# coildriver_new.net
KiCad netlist of a schematic drawn in EasyEDA Pro
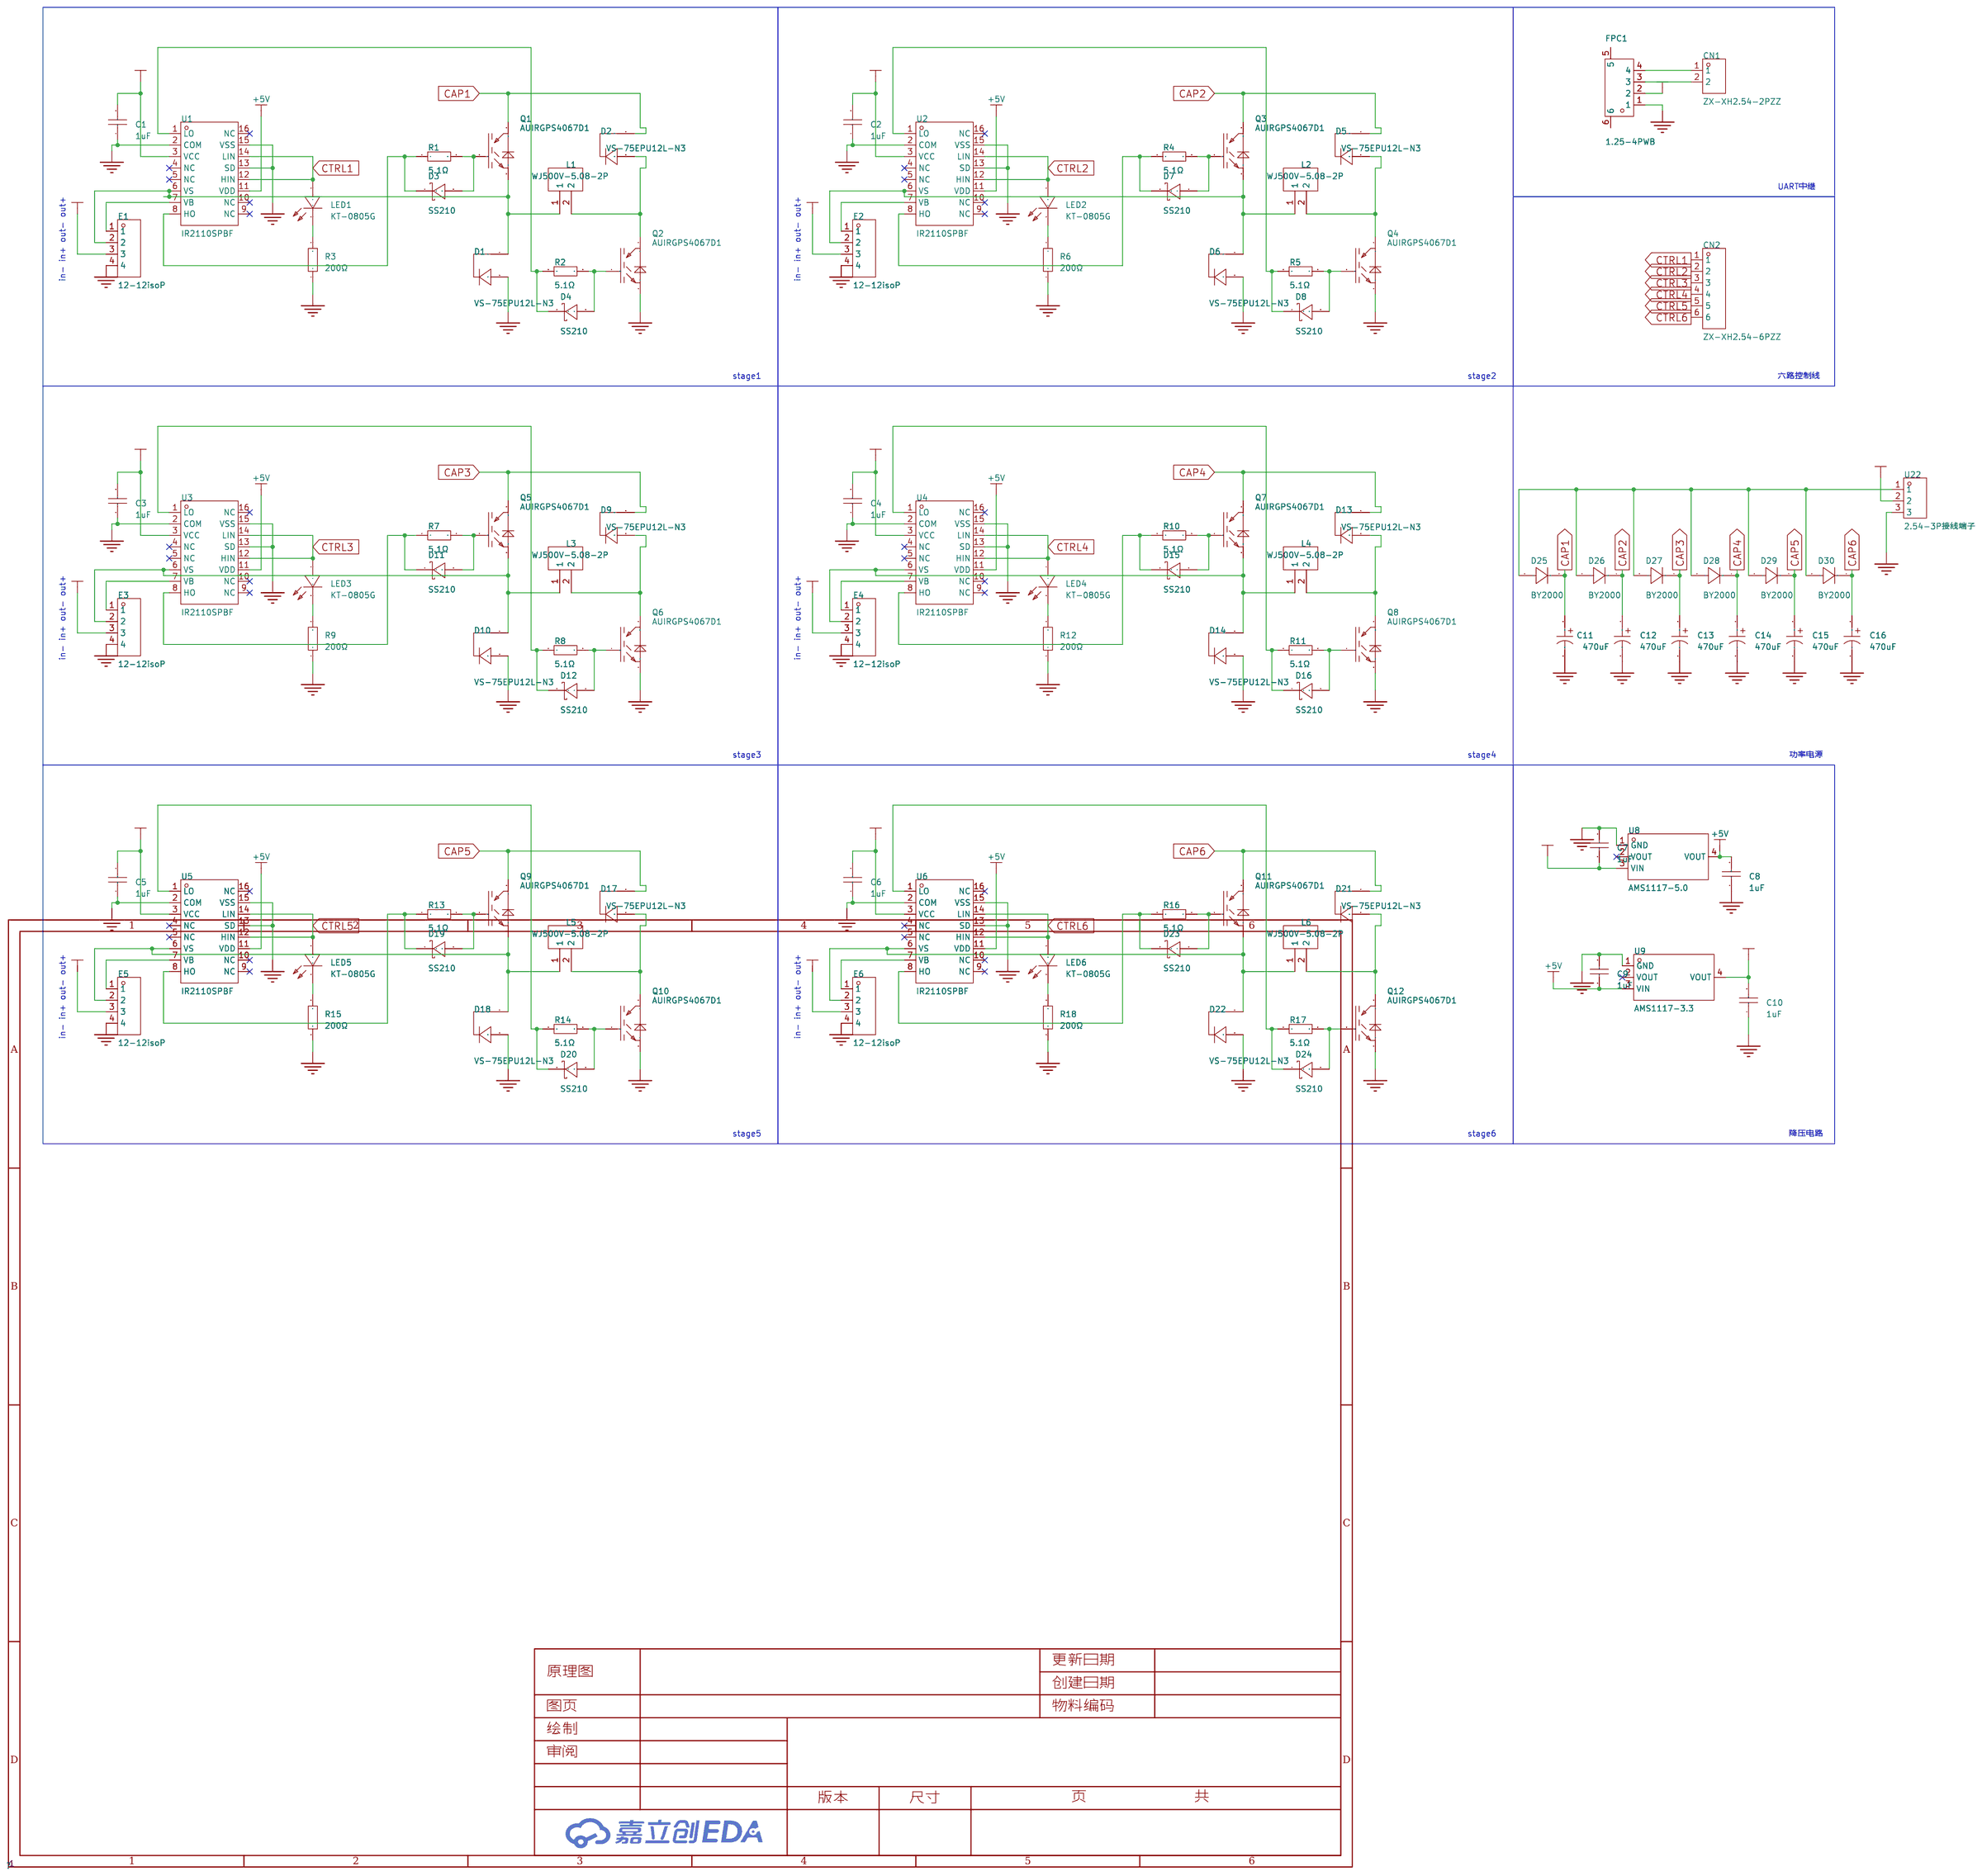
[diagram p0: schematic sheet]

(export (version "E")
  (design (tool "Eeschema 10.0.6"))
  (components
    (comp (ref "C1")
      (value "1uF")
      (footprint "easyedapro:C0805")
      (description "容值:1uF;精度:±10%;额定电压:50V;材质(温度系数):X7R;")
      (fields
        (field (name "Manufacturer Part") "CL21B105KBFNNNE")
        (field (name "Manufacturer") "SAMSUNG(三星)")
      )
      (libsource (lib "easyedapro") (part "CL21B105KBFNNNE"))
    )
    (comp (ref "C2")
      (value "1uF")
      (footprint "easyedapro:C0805")
      (description "容值:1uF;精度:±10%;额定电压:50V;材质(温度系数):X7R;")
      (fields
        (field (name "Manufacturer Part") "CL21B105KBFNNNE")
        (field (name "Manufacturer") "SAMSUNG(三星)")
      )
      (libsource (lib "easyedapro") (part "CL21B105KBFNNNE"))
    )
    (comp (ref "C3")
      (value "1uF")
      (footprint "easyedapro:C0805")
      (description "容值:1uF;精度:±10%;额定电压:50V;材质(温度系数):X7R;")
      (fields
        (field (name "Manufacturer Part") "CL21B105KBFNNNE")
        (field (name "Manufacturer") "SAMSUNG(三星)")
      )
      (libsource (lib "easyedapro") (part "CL21B105KBFNNNE"))
    )
    (comp (ref "C4")
      (value "1uF")
      (footprint "easyedapro:C0805")
      (description "容值:1uF;精度:±10%;额定电压:50V;材质(温度系数):X7R;")
      (fields
        (field (name "Manufacturer Part") "CL21B105KBFNNNE")
        (field (name "Manufacturer") "SAMSUNG(三星)")
      )
      (libsource (lib "easyedapro") (part "CL21B105KBFNNNE"))
    )
    (comp (ref "C5")
      (value "1uF")
      (footprint "easyedapro:C0805")
      (description "容值:1uF;精度:±10%;额定电压:50V;材质(温度系数):X7R;")
      (fields
        (field (name "Manufacturer Part") "CL21B105KBFNNNE")
        (field (name "Manufacturer") "SAMSUNG(三星)")
      )
      (libsource (lib "easyedapro") (part "CL21B105KBFNNNE"))
    )
    (comp (ref "C6")
      (value "1uF")
      (footprint "easyedapro:C0805")
      (description "容值:1uF;精度:±10%;额定电压:50V;材质(温度系数):X7R;")
      (fields
        (field (name "Manufacturer Part") "CL21B105KBFNNNE")
        (field (name "Manufacturer") "SAMSUNG(三星)")
      )
      (libsource (lib "easyedapro") (part "CL21B105KBFNNNE"))
    )
    (comp (ref "C7")
      (value "1uF")
      (footprint "easyedapro:C0805")
      (description "容值:1uF;精度:±10%;额定电压:50V;材质(温度系数):X7R;")
      (fields
        (field (name "Manufacturer Part") "CL21B105KBFNNNE")
        (field (name "Manufacturer") "SAMSUNG(三星)")
      )
      (libsource (lib "easyedapro") (part "CL21B105KBFNNNE"))
    )
    (comp (ref "C8")
      (value "1uF")
      (footprint "easyedapro:C0805")
      (description "容值:1uF;精度:±10%;额定电压:50V;材质(温度系数):X7R;")
      (fields
        (field (name "Manufacturer Part") "CL21B105KBFNNNE")
        (field (name "Manufacturer") "SAMSUNG(三星)")
      )
      (libsource (lib "easyedapro") (part "CL21B105KBFNNNE"))
    )
    (comp (ref "C9")
      (value "1uF")
      (footprint "easyedapro:C0805")
      (description "容值:1uF;精度:±10%;额定电压:50V;材质(温度系数):X7R;")
      (fields
        (field (name "Manufacturer Part") "CL21B105KBFNNNE")
        (field (name "Manufacturer") "SAMSUNG(三星)")
      )
      (libsource (lib "easyedapro") (part "CL21B105KBFNNNE"))
    )
    (comp (ref "C10")
      (value "1uF")
      (footprint "easyedapro:C0805")
      (description "容值:1uF;精度:±10%;额定电压:50V;材质(温度系数):X7R;")
      (fields
        (field (name "Manufacturer Part") "CL21B105KBFNNNE")
        (field (name "Manufacturer") "SAMSUNG(三星)")
      )
      (libsource (lib "easyedapro") (part "CL21B105KBFNNNE"))
    )
    (comp (ref "C11")
      (value "470uF")
      (footprint "easyedapro:CAP-TH_BD35.0-P10.00-D2.3-FD")
      (description "容值:470uF;精度:±20%;额定电压:450V;脚间距:10mm;纹波电流:1.95A@120Hz;")
      (fields
        (field (name "Manufacturer Part") "450MXG470MEFCSN35X40")
        (field (name "Manufacturer") "rubycon(红宝石)")
      )
      (libsource (lib "easyedapro") (part "450MXG470MEFCSN35X40"))
    )
    (comp (ref "C12")
      (value "470uF")
      (footprint "easyedapro:CAP-TH_BD35.0-P10.00-D2.3-FD")
      (description "容值:470uF;精度:±20%;额定电压:450V;脚间距:10mm;纹波电流:1.95A@120Hz;")
      (fields
        (field (name "Manufacturer Part") "450MXG470MEFCSN35X40")
        (field (name "Manufacturer") "rubycon(红宝石)")
      )
      (libsource (lib "easyedapro") (part "450MXG470MEFCSN35X40"))
    )
    (comp (ref "C13")
      (value "470uF")
      (footprint "easyedapro:CAP-TH_BD35.0-P10.00-D2.3-FD")
      (description "容值:470uF;精度:±20%;额定电压:450V;脚间距:10mm;纹波电流:1.95A@120Hz;")
      (fields
        (field (name "Manufacturer Part") "450MXG470MEFCSN35X40")
        (field (name "Manufacturer") "rubycon(红宝石)")
      )
      (libsource (lib "easyedapro") (part "450MXG470MEFCSN35X40"))
    )
    (comp (ref "C14")
      (value "470uF")
      (footprint "easyedapro:CAP-TH_BD35.0-P10.00-D2.3-FD")
      (description "容值:470uF;精度:±20%;额定电压:450V;脚间距:10mm;纹波电流:1.95A@120Hz;")
      (fields
        (field (name "Manufacturer Part") "450MXG470MEFCSN35X40")
        (field (name "Manufacturer") "rubycon(红宝石)")
      )
      (libsource (lib "easyedapro") (part "450MXG470MEFCSN35X40"))
    )
    (comp (ref "C15")
      (value "470uF")
      (footprint "easyedapro:CAP-TH_BD35.0-P10.00-D2.3-FD")
      (description "容值:470uF;精度:±20%;额定电压:450V;脚间距:10mm;纹波电流:1.95A@120Hz;")
      (fields
        (field (name "Manufacturer Part") "450MXG470MEFCSN35X40")
        (field (name "Manufacturer") "rubycon(红宝石)")
      )
      (libsource (lib "easyedapro") (part "450MXG470MEFCSN35X40"))
    )
    (comp (ref "C16")
      (value "470uF")
      (footprint "easyedapro:CAP-TH_BD35.0-P10.00-D2.3-FD")
      (description "容值:470uF;精度:±20%;额定电压:450V;脚间距:10mm;纹波电流:1.95A@120Hz;")
      (fields
        (field (name "Manufacturer Part") "450MXG470MEFCSN35X40")
        (field (name "Manufacturer") "rubycon(红宝石)")
      )
      (libsource (lib "easyedapro") (part "450MXG470MEFCSN35X40"))
    )
    (comp (ref "CN1")
      (value "ZX-XH2.54-2PZZ")
      (footprint "easyedapro:CONN-TH_2P-P2.50_HX25003-2A")
      (fields (field (name "Manufacturer") "Megastar(兆星)"))
      (libsource (lib "easyedapro") (part "ZX-XH2.54-2PZZ"))
    )
    (comp (ref "CN2")
      (value "ZX-XH2.54-6PZZ")
      (footprint "easyedapro:CONN-TH_6P-P2.50_ZX-XH2.54-6PZZ")
      (fields (field (name "Manufacturer") "Megastar(兆星)"))
      (libsource (lib "easyedapro") (part "ZX-XH2.54-6PZZ"))
    )
    (comp (ref "D1")
      (value "VS-75EPU12L-N3")
      (footprint "easyedapro:TO-247-2_L15.8-W5.0-P10.92-L")
      (description "二极管配置:独立式;正向压降(Vf):2.05V@75A;直流反向耐压(Vr):1.2kV;平均整流电流(Io):75A;")
      (fields (field (name "Manufacturer") "VISHAY(威世)"))
      (libsource (lib "easyedapro") (part "VS-75EPU12L-N3"))
    )
    (comp (ref "D2")
      (value "VS-75EPU12L-N3")
      (footprint "easyedapro:TO-247-2_L15.8-W5.0-P10.92-L")
      (description "二极管配置:独立式;正向压降(Vf):2.05V@75A;直流反向耐压(Vr):1.2kV;平均整流电流(Io):75A;")
      (fields (field (name "Manufacturer") "VISHAY(威世)"))
      (libsource (lib "easyedapro") (part "VS-75EPU12L-N3"))
    )
    (comp (ref "D3")
      (value "SS210")
      (footprint "easyedapro:SMA_L4.3-W2.6-LS5.2-RD")
      (description "正向压降(Vf):850mV@2A;直流反向耐压(Vr):100V;整流电流:2A;")
      (fields (field (name "Manufacturer") "MDD(辰达半导体)"))
      (libsource (lib "easyedapro") (part "SS210"))
    )
    (comp (ref "D4")
      (value "SS210")
      (footprint "easyedapro:SMA_L4.3-W2.6-LS5.2-RD")
      (description "正向压降(Vf):850mV@2A;直流反向耐压(Vr):100V;整流电流:2A;")
      (fields (field (name "Manufacturer") "MDD(辰达半导体)"))
      (libsource (lib "easyedapro") (part "SS210"))
    )
    (comp (ref "D5")
      (value "VS-75EPU12L-N3")
      (footprint "easyedapro:TO-247-2_L15.8-W5.0-P10.92-L")
      (description "二极管配置:独立式;正向压降(Vf):2.05V@75A;直流反向耐压(Vr):1.2kV;平均整流电流(Io):75A;")
      (fields (field (name "Manufacturer") "VISHAY(威世)"))
      (libsource (lib "easyedapro") (part "VS-75EPU12L-N3"))
    )
    (comp (ref "D6")
      (value "VS-75EPU12L-N3")
      (footprint "easyedapro:TO-247-2_L15.8-W5.0-P10.92-L")
      (description "二极管配置:独立式;正向压降(Vf):2.05V@75A;直流反向耐压(Vr):1.2kV;平均整流电流(Io):75A;")
      (fields (field (name "Manufacturer") "VISHAY(威世)"))
      (libsource (lib "easyedapro") (part "VS-75EPU12L-N3"))
    )
    (comp (ref "D7")
      (value "SS210")
      (footprint "easyedapro:SMA_L4.3-W2.6-LS5.2-RD")
      (description "正向压降(Vf):850mV@2A;直流反向耐压(Vr):100V;整流电流:2A;")
      (fields (field (name "Manufacturer") "MDD(辰达半导体)"))
      (libsource (lib "easyedapro") (part "SS210"))
    )
    (comp (ref "D8")
      (value "SS210")
      (footprint "easyedapro:SMA_L4.3-W2.6-LS5.2-RD")
      (description "正向压降(Vf):850mV@2A;直流反向耐压(Vr):100V;整流电流:2A;")
      (fields (field (name "Manufacturer") "MDD(辰达半导体)"))
      (libsource (lib "easyedapro") (part "SS210"))
    )
    (comp (ref "D9")
      (value "VS-75EPU12L-N3")
      (footprint "easyedapro:TO-247-2_L15.8-W5.0-P10.92-L")
      (description "二极管配置:独立式;正向压降(Vf):2.05V@75A;直流反向耐压(Vr):1.2kV;平均整流电流(Io):75A;")
      (fields (field (name "Manufacturer") "VISHAY(威世)"))
      (libsource (lib "easyedapro") (part "VS-75EPU12L-N3"))
    )
    (comp (ref "D10")
      (value "VS-75EPU12L-N3")
      (footprint "easyedapro:TO-247-2_L15.8-W5.0-P10.92-L")
      (description "二极管配置:独立式;正向压降(Vf):2.05V@75A;直流反向耐压(Vr):1.2kV;平均整流电流(Io):75A;")
      (fields (field (name "Manufacturer") "VISHAY(威世)"))
      (libsource (lib "easyedapro") (part "VS-75EPU12L-N3"))
    )
    (comp (ref "D11")
      (value "SS210")
      (footprint "easyedapro:SMA_L4.3-W2.6-LS5.2-RD")
      (description "正向压降(Vf):850mV@2A;直流反向耐压(Vr):100V;整流电流:2A;")
      (fields (field (name "Manufacturer") "MDD(辰达半导体)"))
      (libsource (lib "easyedapro") (part "SS210"))
    )
    (comp (ref "D12")
      (value "SS210")
      (footprint "easyedapro:SMA_L4.3-W2.6-LS5.2-RD")
      (description "正向压降(Vf):850mV@2A;直流反向耐压(Vr):100V;整流电流:2A;")
      (fields (field (name "Manufacturer") "MDD(辰达半导体)"))
      (libsource (lib "easyedapro") (part "SS210"))
    )
    (comp (ref "D13")
      (value "VS-75EPU12L-N3")
      (footprint "easyedapro:TO-247-2_L15.8-W5.0-P10.92-L")
      (description "二极管配置:独立式;正向压降(Vf):2.05V@75A;直流反向耐压(Vr):1.2kV;平均整流电流(Io):75A;")
      (fields (field (name "Manufacturer") "VISHAY(威世)"))
      (libsource (lib "easyedapro") (part "VS-75EPU12L-N3"))
    )
    (comp (ref "D14")
      (value "VS-75EPU12L-N3")
      (footprint "easyedapro:TO-247-2_L15.8-W5.0-P10.92-L")
      (description "二极管配置:独立式;正向压降(Vf):2.05V@75A;直流反向耐压(Vr):1.2kV;平均整流电流(Io):75A;")
      (fields (field (name "Manufacturer") "VISHAY(威世)"))
      (libsource (lib "easyedapro") (part "VS-75EPU12L-N3"))
    )
    (comp (ref "D15")
      (value "SS210")
      (footprint "easyedapro:SMA_L4.3-W2.6-LS5.2-RD")
      (description "正向压降(Vf):850mV@2A;直流反向耐压(Vr):100V;整流电流:2A;")
      (fields (field (name "Manufacturer") "MDD(辰达半导体)"))
      (libsource (lib "easyedapro") (part "SS210"))
    )
    (comp (ref "D16")
      (value "SS210")
      (footprint "easyedapro:SMA_L4.3-W2.6-LS5.2-RD")
      (description "正向压降(Vf):850mV@2A;直流反向耐压(Vr):100V;整流电流:2A;")
      (fields (field (name "Manufacturer") "MDD(辰达半导体)"))
      (libsource (lib "easyedapro") (part "SS210"))
    )
    (comp (ref "D17")
      (value "VS-75EPU12L-N3")
      (footprint "easyedapro:TO-247-2_L15.8-W5.0-P10.92-L")
      (description "二极管配置:独立式;正向压降(Vf):2.05V@75A;直流反向耐压(Vr):1.2kV;平均整流电流(Io):75A;")
      (fields (field (name "Manufacturer") "VISHAY(威世)"))
      (libsource (lib "easyedapro") (part "VS-75EPU12L-N3"))
    )
    (comp (ref "D18")
      (value "VS-75EPU12L-N3")
      (footprint "easyedapro:TO-247-2_L15.8-W5.0-P10.92-L")
      (description "二极管配置:独立式;正向压降(Vf):2.05V@75A;直流反向耐压(Vr):1.2kV;平均整流电流(Io):75A;")
      (fields (field (name "Manufacturer") "VISHAY(威世)"))
      (libsource (lib "easyedapro") (part "VS-75EPU12L-N3"))
    )
    (comp (ref "D19")
      (value "SS210")
      (footprint "easyedapro:SMA_L4.3-W2.6-LS5.2-RD")
      (description "正向压降(Vf):850mV@2A;直流反向耐压(Vr):100V;整流电流:2A;")
      (fields (field (name "Manufacturer") "MDD(辰达半导体)"))
      (libsource (lib "easyedapro") (part "SS210"))
    )
    (comp (ref "D20")
      (value "SS210")
      (footprint "easyedapro:SMA_L4.3-W2.6-LS5.2-RD")
      (description "正向压降(Vf):850mV@2A;直流反向耐压(Vr):100V;整流电流:2A;")
      (fields (field (name "Manufacturer") "MDD(辰达半导体)"))
      (libsource (lib "easyedapro") (part "SS210"))
    )
    (comp (ref "D21")
      (value "VS-75EPU12L-N3")
      (footprint "easyedapro:TO-247-2_L15.8-W5.0-P10.92-L")
      (description "二极管配置:独立式;正向压降(Vf):2.05V@75A;直流反向耐压(Vr):1.2kV;平均整流电流(Io):75A;")
      (fields (field (name "Manufacturer") "VISHAY(威世)"))
      (libsource (lib "easyedapro") (part "VS-75EPU12L-N3"))
    )
    (comp (ref "D22")
      (value "VS-75EPU12L-N3")
      (footprint "easyedapro:TO-247-2_L15.8-W5.0-P10.92-L")
      (description "二极管配置:独立式;正向压降(Vf):2.05V@75A;直流反向耐压(Vr):1.2kV;平均整流电流(Io):75A;")
      (fields (field (name "Manufacturer") "VISHAY(威世)"))
      (libsource (lib "easyedapro") (part "VS-75EPU12L-N3"))
    )
    (comp (ref "D23")
      (value "SS210")
      (footprint "easyedapro:SMA_L4.3-W2.6-LS5.2-RD")
      (description "正向压降(Vf):850mV@2A;直流反向耐压(Vr):100V;整流电流:2A;")
      (fields (field (name "Manufacturer") "MDD(辰达半导体)"))
      (libsource (lib "easyedapro") (part "SS210"))
    )
    (comp (ref "D24")
      (value "SS210")
      (footprint "easyedapro:SMA_L4.3-W2.6-LS5.2-RD")
      (description "正向压降(Vf):850mV@2A;直流反向耐压(Vr):100V;整流电流:2A;")
      (fields (field (name "Manufacturer") "MDD(辰达半导体)"))
      (libsource (lib "easyedapro") (part "SS210"))
    )
    (comp (ref "D25")
      (value "BY2000")
      (footprint "easyedapro:DO-201_BD4.5-L7.5-P11.50-D1.2-RD")
      (description "正向压降(Vf):1.1V@3A;直流反向耐压(Vr):2kV;整流电流:3A;")
      (fields (field (name "Manufacturer") "DIOTEC(德欧泰克)"))
      (libsource (lib "easyedapro") (part "BY2000"))
    )
    (comp (ref "D26")
      (value "BY2000")
      (footprint "easyedapro:DO-201_BD4.5-L7.5-P11.50-D1.2-RD")
      (description "正向压降(Vf):1.1V@3A;直流反向耐压(Vr):2kV;整流电流:3A;")
      (fields (field (name "Manufacturer") "DIOTEC(德欧泰克)"))
      (libsource (lib "easyedapro") (part "BY2000"))
    )
    (comp (ref "D27")
      (value "BY2000")
      (footprint "easyedapro:DO-201_BD4.5-L7.5-P11.50-D1.2-RD")
      (description "正向压降(Vf):1.1V@3A;直流反向耐压(Vr):2kV;整流电流:3A;")
      (fields (field (name "Manufacturer") "DIOTEC(德欧泰克)"))
      (libsource (lib "easyedapro") (part "BY2000"))
    )
    (comp (ref "D28")
      (value "BY2000")
      (footprint "easyedapro:DO-201_BD4.5-L7.5-P11.50-D1.2-RD")
      (description "正向压降(Vf):1.1V@3A;直流反向耐压(Vr):2kV;整流电流:3A;")
      (fields (field (name "Manufacturer") "DIOTEC(德欧泰克)"))
      (libsource (lib "easyedapro") (part "BY2000"))
    )
    (comp (ref "D29")
      (value "BY2000")
      (footprint "easyedapro:DO-201_BD4.5-L7.5-P11.50-D1.2-RD")
      (description "正向压降(Vf):1.1V@3A;直流反向耐压(Vr):2kV;整流电流:3A;")
      (fields (field (name "Manufacturer") "DIOTEC(德欧泰克)"))
      (libsource (lib "easyedapro") (part "BY2000"))
    )
    (comp (ref "D30")
      (value "BY2000")
      (footprint "easyedapro:DO-201_BD4.5-L7.5-P11.50-D1.2-RD")
      (description "正向压降(Vf):1.1V@3A;直流反向耐压(Vr):2kV;整流电流:3A;")
      (fields (field (name "Manufacturer") "DIOTEC(德欧泰克)"))
      (libsource (lib "easyedapro") (part "BY2000"))
    )
    (comp (ref "E1")
      (value "12-12isoP")
      (footprint "easyedapro:HDR-TH_4P-P2.54-V-M")
      (fields (field (name "Manufacturer") "XFCN(兴飞)"))
      (libsource (lib "easyedapro") (part "PZ254V-11-04P_C2691448"))
    )
    (comp (ref "E2")
      (value "12-12isoP")
      (footprint "easyedapro:HDR-TH_4P-P2.54-V-M")
      (fields (field (name "Manufacturer") "XFCN(兴飞)"))
      (libsource (lib "easyedapro") (part "PZ254V-11-04P_C2691448"))
    )
    (comp (ref "E3")
      (value "12-12isoP")
      (footprint "easyedapro:HDR-TH_4P-P2.54-V-M")
      (fields (field (name "Manufacturer") "XFCN(兴飞)"))
      (libsource (lib "easyedapro") (part "PZ254V-11-04P_C2691448"))
    )
    (comp (ref "E4")
      (value "12-12isoP")
      (footprint "easyedapro:HDR-TH_4P-P2.54-V-M")
      (fields (field (name "Manufacturer") "XFCN(兴飞)"))
      (libsource (lib "easyedapro") (part "PZ254V-11-04P_C2691448"))
    )
    (comp (ref "E5")
      (value "12-12isoP")
      (footprint "easyedapro:HDR-TH_4P-P2.54-V-M")
      (fields (field (name "Manufacturer") "XFCN(兴飞)"))
      (libsource (lib "easyedapro") (part "PZ254V-11-04P_C2691448"))
    )
    (comp (ref "E6")
      (value "12-12isoP")
      (footprint "easyedapro:HDR-TH_4P-P2.54-V-M")
      (fields (field (name "Manufacturer") "XFCN(兴飞)"))
      (libsource (lib "easyedapro") (part "PZ254V-11-04P_C2691448"))
    )
    (comp (ref "FPC1")
      (value "1.25-4PWB")
      (footprint "easyedapro:CONN-SMD_1.25-4PWB")
      (description "插针结构:1x4P;间距:1.25mm;安装方式:卧贴;参考系列:-;总PIN数:4P;排数:1;每排PIN数:4;行距:-;额定电流:-;工作温度范围:-40°C~+85°C;")
      (fields (field (name "Manufacturer") "DEALON(德艺隆)"))
      (libsource (lib "easyedapro") (part "1.25-4PWB"))
    )
    (comp (ref "L1")
      (value "WJ500V-5.08-2P")
      (footprint "easyedapro:CONN-TH_2P-P5.00_WJ500V-5.08-2P")
      (fields (field (name "Manufacturer") "KANGNEX(康奈克斯电气)"))
      (libsource (lib "easyedapro") (part "WJ500V-5.08-2P-14-00A"))
    )
    (comp (ref "L2")
      (value "WJ500V-5.08-2P")
      (footprint "easyedapro:CONN-TH_2P-P5.00_WJ500V-5.08-2P")
      (fields (field (name "Manufacturer") "KANGNEX(康奈克斯电气)"))
      (libsource (lib "easyedapro") (part "WJ500V-5.08-2P-14-00A"))
    )
    (comp (ref "L3")
      (value "WJ500V-5.08-2P")
      (footprint "easyedapro:CONN-TH_2P-P5.00_WJ500V-5.08-2P")
      (fields (field (name "Manufacturer") "KANGNEX(康奈克斯电气)"))
      (libsource (lib "easyedapro") (part "WJ500V-5.08-2P-14-00A"))
    )
    (comp (ref "L4")
      (value "WJ500V-5.08-2P")
      (footprint "easyedapro:CONN-TH_2P-P5.00_WJ500V-5.08-2P")
      (fields (field (name "Manufacturer") "KANGNEX(康奈克斯电气)"))
      (libsource (lib "easyedapro") (part "WJ500V-5.08-2P-14-00A"))
    )
    (comp (ref "L5")
      (value "WJ500V-5.08-2P")
      (footprint "easyedapro:CONN-TH_2P-P5.00_WJ500V-5.08-2P")
      (fields (field (name "Manufacturer") "KANGNEX(康奈克斯电气)"))
      (libsource (lib "easyedapro") (part "WJ500V-5.08-2P-14-00A"))
    )
    (comp (ref "L6")
      (value "WJ500V-5.08-2P")
      (footprint "easyedapro:CONN-TH_2P-P5.00_WJ500V-5.08-2P")
      (fields (field (name "Manufacturer") "KANGNEX(康奈克斯电气)"))
      (libsource (lib "easyedapro") (part "WJ500V-5.08-2P-14-00A"))
    )
    (comp (ref "LED1")
      (value "KT-0805G")
      (footprint "easyedapro:LED0805-R-RD")
      (description "灯头类型:-;发光颜色:翠绿色;正向电压(VF):-;功率:-;正向电流:-;主波长:-;二极管配置:-;透镜颜色:-;色温:-;发光强度:-;发光角度:-;载带方式:-;工作温度:-;")
      (fields (field (name "Manufacturer") "KENTO"))
      (libsource (lib "easyedapro") (part "0805G (Green)"))
    )
    (comp (ref "LED2")
      (value "KT-0805G")
      (footprint "easyedapro:LED0805-R-RD")
      (description "灯头类型:-;发光颜色:翠绿色;正向电压(VF):-;功率:-;正向电流:-;主波长:-;二极管配置:-;透镜颜色:-;色温:-;发光强度:-;发光角度:-;载带方式:-;工作温度:-;")
      (fields (field (name "Manufacturer") "KENTO"))
      (libsource (lib "easyedapro") (part "0805G (Green)"))
    )
    (comp (ref "LED3")
      (value "KT-0805G")
      (footprint "easyedapro:LED0805-R-RD")
      (description "灯头类型:-;发光颜色:翠绿色;正向电压(VF):-;功率:-;正向电流:-;主波长:-;二极管配置:-;透镜颜色:-;色温:-;发光强度:-;发光角度:-;载带方式:-;工作温度:-;")
      (fields (field (name "Manufacturer") "KENTO"))
      (libsource (lib "easyedapro") (part "0805G (Green)"))
    )
    (comp (ref "LED4")
      (value "KT-0805G")
      (footprint "easyedapro:LED0805-R-RD")
      (description "灯头类型:-;发光颜色:翠绿色;正向电压(VF):-;功率:-;正向电流:-;主波长:-;二极管配置:-;透镜颜色:-;色温:-;发光强度:-;发光角度:-;载带方式:-;工作温度:-;")
      (fields (field (name "Manufacturer") "KENTO"))
      (libsource (lib "easyedapro") (part "0805G (Green)"))
    )
    (comp (ref "LED5")
      (value "KT-0805G")
      (footprint "easyedapro:LED0805-R-RD")
      (description "灯头类型:-;发光颜色:翠绿色;正向电压(VF):-;功率:-;正向电流:-;主波长:-;二极管配置:-;透镜颜色:-;色温:-;发光强度:-;发光角度:-;载带方式:-;工作温度:-;")
      (fields (field (name "Manufacturer") "KENTO"))
      (libsource (lib "easyedapro") (part "0805G (Green)"))
    )
    (comp (ref "LED6")
      (value "KT-0805G")
      (footprint "easyedapro:LED0805-R-RD")
      (description "灯头类型:-;发光颜色:翠绿色;正向电压(VF):-;功率:-;正向电流:-;主波长:-;二极管配置:-;透镜颜色:-;色温:-;发光强度:-;发光角度:-;载带方式:-;工作温度:-;")
      (fields (field (name "Manufacturer") "KENTO"))
      (libsource (lib "easyedapro") (part "0805G (Green)"))
    )
    (comp (ref "Q1")
      (value "AUIRGPS4067D1")
      (footprint "easyedapro:SUPER-247_L15.6-W5.0-P5.45-L")
      (libsource (lib "easyedapro") (part "AUIRGPS4067D1"))
    )
    (comp (ref "Q2")
      (value "AUIRGPS4067D1")
      (footprint "easyedapro:SUPER-247_L15.6-W5.0-P5.45-L")
      (libsource (lib "easyedapro") (part "AUIRGPS4067D1"))
    )
    (comp (ref "Q3")
      (value "AUIRGPS4067D1")
      (footprint "easyedapro:SUPER-247_L15.6-W5.0-P5.45-L")
      (libsource (lib "easyedapro") (part "AUIRGPS4067D1"))
    )
    (comp (ref "Q4")
      (value "AUIRGPS4067D1")
      (footprint "easyedapro:SUPER-247_L15.6-W5.0-P5.45-L")
      (libsource (lib "easyedapro") (part "AUIRGPS4067D1"))
    )
    (comp (ref "Q5")
      (value "AUIRGPS4067D1")
      (footprint "easyedapro:SUPER-247_L15.6-W5.0-P5.45-L")
      (libsource (lib "easyedapro") (part "AUIRGPS4067D1"))
    )
    (comp (ref "Q6")
      (value "AUIRGPS4067D1")
      (footprint "easyedapro:SUPER-247_L15.6-W5.0-P5.45-L")
      (libsource (lib "easyedapro") (part "AUIRGPS4067D1"))
    )
    (comp (ref "Q7")
      (value "AUIRGPS4067D1")
      (footprint "easyedapro:SUPER-247_L15.6-W5.0-P5.45-L")
      (libsource (lib "easyedapro") (part "AUIRGPS4067D1"))
    )
    (comp (ref "Q8")
      (value "AUIRGPS4067D1")
      (footprint "easyedapro:SUPER-247_L15.6-W5.0-P5.45-L")
      (libsource (lib "easyedapro") (part "AUIRGPS4067D1"))
    )
    (comp (ref "Q9")
      (value "AUIRGPS4067D1")
      (footprint "easyedapro:SUPER-247_L15.6-W5.0-P5.45-L")
      (libsource (lib "easyedapro") (part "AUIRGPS4067D1"))
    )
    (comp (ref "Q10")
      (value "AUIRGPS4067D1")
      (footprint "easyedapro:SUPER-247_L15.6-W5.0-P5.45-L")
      (libsource (lib "easyedapro") (part "AUIRGPS4067D1"))
    )
    (comp (ref "Q11")
      (value "AUIRGPS4067D1")
      (footprint "easyedapro:SUPER-247_L15.6-W5.0-P5.45-L")
      (libsource (lib "easyedapro") (part "AUIRGPS4067D1"))
    )
    (comp (ref "Q12")
      (value "AUIRGPS4067D1")
      (footprint "easyedapro:SUPER-247_L15.6-W5.0-P5.45-L")
      (libsource (lib "easyedapro") (part "AUIRGPS4067D1"))
    )
    (comp (ref "R1")
      (value "5.1Ω")
      (footprint "easyedapro:R0805")
      (description "电阻类型:厚膜电阻;阻值:5.1Ω;精度:±1%;功率:125mW;最大工作电压:150V;温度系数:±400ppm/°C;")
      (fields
        (field (name "Manufacturer Part") "0805W8F510KT5E")
        (field (name "Manufacturer") "UNI-ROYAL(厚声)")
      )
      (libsource (lib "easyedapro") (part "0805W8F510KT5E"))
    )
    (comp (ref "R2")
      (value "5.1Ω")
      (footprint "easyedapro:R0805")
      (description "电阻类型:厚膜电阻;阻值:5.1Ω;精度:±1%;功率:125mW;最大工作电压:150V;温度系数:±400ppm/°C;")
      (fields
        (field (name "Manufacturer Part") "0805W8F510KT5E")
        (field (name "Manufacturer") "UNI-ROYAL(厚声)")
      )
      (libsource (lib "easyedapro") (part "0805W8F510KT5E"))
    )
    (comp (ref "R3")
      (value "200Ω")
      (footprint "easyedapro:R0603")
      (description "电阻类型:厚膜电阻;阻值:200Ω;精度:±1%;功率:100mW;最大工作电压:75V;温度系数:±100ppm/°C;")
      (fields
        (field (name "Manufacturer Part") "0603WAF2000T5E")
        (field (name "Manufacturer") "UNI-ROYAL(厚声)")
      )
      (libsource (lib "easyedapro") (part "0603WAF2000T5E"))
    )
    (comp (ref "R4")
      (value "5.1Ω")
      (footprint "easyedapro:R0805")
      (description "电阻类型:厚膜电阻;阻值:5.1Ω;精度:±1%;功率:125mW;最大工作电压:150V;温度系数:±400ppm/°C;")
      (fields
        (field (name "Manufacturer Part") "0805W8F510KT5E")
        (field (name "Manufacturer") "UNI-ROYAL(厚声)")
      )
      (libsource (lib "easyedapro") (part "0805W8F510KT5E"))
    )
    (comp (ref "R5")
      (value "5.1Ω")
      (footprint "easyedapro:R0805")
      (description "电阻类型:厚膜电阻;阻值:5.1Ω;精度:±1%;功率:125mW;最大工作电压:150V;温度系数:±400ppm/°C;")
      (fields
        (field (name "Manufacturer Part") "0805W8F510KT5E")
        (field (name "Manufacturer") "UNI-ROYAL(厚声)")
      )
      (libsource (lib "easyedapro") (part "0805W8F510KT5E"))
    )
    (comp (ref "R6")
      (value "200Ω")
      (footprint "easyedapro:R0603")
      (description "电阻类型:厚膜电阻;阻值:200Ω;精度:±1%;功率:100mW;最大工作电压:75V;温度系数:±100ppm/°C;")
      (fields
        (field (name "Manufacturer Part") "0603WAF2000T5E")
        (field (name "Manufacturer") "UNI-ROYAL(厚声)")
      )
      (libsource (lib "easyedapro") (part "0603WAF2000T5E"))
    )
    (comp (ref "R7")
      (value "5.1Ω")
      (footprint "easyedapro:R0805")
      (description "电阻类型:厚膜电阻;阻值:5.1Ω;精度:±1%;功率:125mW;最大工作电压:150V;温度系数:±400ppm/°C;")
      (fields
        (field (name "Manufacturer Part") "0805W8F510KT5E")
        (field (name "Manufacturer") "UNI-ROYAL(厚声)")
      )
      (libsource (lib "easyedapro") (part "0805W8F510KT5E"))
    )
    (comp (ref "R8")
      (value "5.1Ω")
      (footprint "easyedapro:R0805")
      (description "电阻类型:厚膜电阻;阻值:5.1Ω;精度:±1%;功率:125mW;最大工作电压:150V;温度系数:±400ppm/°C;")
      (fields
        (field (name "Manufacturer Part") "0805W8F510KT5E")
        (field (name "Manufacturer") "UNI-ROYAL(厚声)")
      )
      (libsource (lib "easyedapro") (part "0805W8F510KT5E"))
    )
    (comp (ref "R9")
      (value "200Ω")
      (footprint "easyedapro:R0603")
      (description "电阻类型:厚膜电阻;阻值:200Ω;精度:±1%;功率:100mW;最大工作电压:75V;温度系数:±100ppm/°C;")
      (fields
        (field (name "Manufacturer Part") "0603WAF2000T5E")
        (field (name "Manufacturer") "UNI-ROYAL(厚声)")
      )
      (libsource (lib "easyedapro") (part "0603WAF2000T5E"))
    )
    (comp (ref "R10")
      (value "5.1Ω")
      (footprint "easyedapro:R0805")
      (description "电阻类型:厚膜电阻;阻值:5.1Ω;精度:±1%;功率:125mW;最大工作电压:150V;温度系数:±400ppm/°C;")
      (fields
        (field (name "Manufacturer Part") "0805W8F510KT5E")
        (field (name "Manufacturer") "UNI-ROYAL(厚声)")
      )
      (libsource (lib "easyedapro") (part "0805W8F510KT5E"))
    )
    (comp (ref "R11")
      (value "5.1Ω")
      (footprint "easyedapro:R0805")
      (description "电阻类型:厚膜电阻;阻值:5.1Ω;精度:±1%;功率:125mW;最大工作电压:150V;温度系数:±400ppm/°C;")
      (fields
        (field (name "Manufacturer Part") "0805W8F510KT5E")
        (field (name "Manufacturer") "UNI-ROYAL(厚声)")
      )
      (libsource (lib "easyedapro") (part "0805W8F510KT5E"))
    )
    (comp (ref "R12")
      (value "200Ω")
      (footprint "easyedapro:R0603")
      (description "电阻类型:厚膜电阻;阻值:200Ω;精度:±1%;功率:100mW;最大工作电压:75V;温度系数:±100ppm/°C;")
      (fields
        (field (name "Manufacturer Part") "0603WAF2000T5E")
        (field (name "Manufacturer") "UNI-ROYAL(厚声)")
      )
      (libsource (lib "easyedapro") (part "0603WAF2000T5E"))
    )
    (comp (ref "R13")
      (value "5.1Ω")
      (footprint "easyedapro:R0805")
      (description "电阻类型:厚膜电阻;阻值:5.1Ω;精度:±1%;功率:125mW;最大工作电压:150V;温度系数:±400ppm/°C;")
      (fields
        (field (name "Manufacturer Part") "0805W8F510KT5E")
        (field (name "Manufacturer") "UNI-ROYAL(厚声)")
      )
      (libsource (lib "easyedapro") (part "0805W8F510KT5E"))
    )
    (comp (ref "R14")
      (value "5.1Ω")
      (footprint "easyedapro:R0805")
      (description "电阻类型:厚膜电阻;阻值:5.1Ω;精度:±1%;功率:125mW;最大工作电压:150V;温度系数:±400ppm/°C;")
      (fields
        (field (name "Manufacturer Part") "0805W8F510KT5E")
        (field (name "Manufacturer") "UNI-ROYAL(厚声)")
      )
      (libsource (lib "easyedapro") (part "0805W8F510KT5E"))
    )
    (comp (ref "R15")
      (value "200Ω")
      (footprint "easyedapro:R0603")
      (description "电阻类型:厚膜电阻;阻值:200Ω;精度:±1%;功率:100mW;最大工作电压:75V;温度系数:±100ppm/°C;")
      (fields
        (field (name "Manufacturer Part") "0603WAF2000T5E")
        (field (name "Manufacturer") "UNI-ROYAL(厚声)")
      )
      (libsource (lib "easyedapro") (part "0603WAF2000T5E"))
    )
    (comp (ref "R16")
      (value "5.1Ω")
      (footprint "easyedapro:R0805")
      (description "电阻类型:厚膜电阻;阻值:5.1Ω;精度:±1%;功率:125mW;最大工作电压:150V;温度系数:±400ppm/°C;")
      (fields
        (field (name "Manufacturer Part") "0805W8F510KT5E")
        (field (name "Manufacturer") "UNI-ROYAL(厚声)")
      )
      (libsource (lib "easyedapro") (part "0805W8F510KT5E"))
    )
    (comp (ref "R17")
      (value "5.1Ω")
      (footprint "easyedapro:R0805")
      (description "电阻类型:厚膜电阻;阻值:5.1Ω;精度:±1%;功率:125mW;最大工作电压:150V;温度系数:±400ppm/°C;")
      (fields
        (field (name "Manufacturer Part") "0805W8F510KT5E")
        (field (name "Manufacturer") "UNI-ROYAL(厚声)")
      )
      (libsource (lib "easyedapro") (part "0805W8F510KT5E"))
    )
    (comp (ref "R18")
      (value "200Ω")
      (footprint "easyedapro:R0603")
      (description "电阻类型:厚膜电阻;阻值:200Ω;精度:±1%;功率:100mW;最大工作电压:75V;温度系数:±100ppm/°C;")
      (fields
        (field (name "Manufacturer Part") "0603WAF2000T5E")
        (field (name "Manufacturer") "UNI-ROYAL(厚声)")
      )
      (libsource (lib "easyedapro") (part "0603WAF2000T5E"))
    )
    (comp (ref "U1")
      (value "IR2110SPBF")
      (footprint "easyedapro:SOIC-16_L10.3-W7.5-P1.27-LS10.3-BL")
      (description "驱动配置:半桥;负载类型:MOSFET；IGBT;驱动通道数:2;峰值灌电流:2A;峰值拉电流:2A;电源电压:3.3V~20V;上升时间:25ns;下降时间:17ns;")
      (fields (field (name "Manufacturer") "Infineon(英飞凌)"))
      (libsource (lib "easyedapro") (part "IR2110SPBF"))
    )
    (comp (ref "U2")
      (value "IR2110SPBF")
      (footprint "easyedapro:SOIC-16_L10.3-W7.5-P1.27-LS10.3-BL")
      (description "驱动配置:半桥;负载类型:MOSFET；IGBT;驱动通道数:2;峰值灌电流:2A;峰值拉电流:2A;电源电压:3.3V~20V;上升时间:25ns;下降时间:17ns;")
      (fields (field (name "Manufacturer") "Infineon(英飞凌)"))
      (libsource (lib "easyedapro") (part "IR2110SPBF"))
    )
    (comp (ref "U3")
      (value "IR2110SPBF")
      (footprint "easyedapro:SOIC-16_L10.3-W7.5-P1.27-LS10.3-BL")
      (description "驱动配置:半桥;负载类型:MOSFET；IGBT;驱动通道数:2;峰值灌电流:2A;峰值拉电流:2A;电源电压:3.3V~20V;上升时间:25ns;下降时间:17ns;")
      (fields (field (name "Manufacturer") "Infineon(英飞凌)"))
      (libsource (lib "easyedapro") (part "IR2110SPBF"))
    )
    (comp (ref "U4")
      (value "IR2110SPBF")
      (footprint "easyedapro:SOIC-16_L10.3-W7.5-P1.27-LS10.3-BL")
      (description "驱动配置:半桥;负载类型:MOSFET；IGBT;驱动通道数:2;峰值灌电流:2A;峰值拉电流:2A;电源电压:3.3V~20V;上升时间:25ns;下降时间:17ns;")
      (fields (field (name "Manufacturer") "Infineon(英飞凌)"))
      (libsource (lib "easyedapro") (part "IR2110SPBF"))
    )
    (comp (ref "U5")
      (value "IR2110SPBF")
      (footprint "easyedapro:SOIC-16_L10.3-W7.5-P1.27-LS10.3-BL")
      (description "驱动配置:半桥;负载类型:MOSFET；IGBT;驱动通道数:2;峰值灌电流:2A;峰值拉电流:2A;电源电压:3.3V~20V;上升时间:25ns;下降时间:17ns;")
      (fields (field (name "Manufacturer") "Infineon(英飞凌)"))
      (libsource (lib "easyedapro") (part "IR2110SPBF"))
    )
    (comp (ref "U6")
      (value "IR2110SPBF")
      (footprint "easyedapro:SOIC-16_L10.3-W7.5-P1.27-LS10.3-BL")
      (description "驱动配置:半桥;负载类型:MOSFET；IGBT;驱动通道数:2;峰值灌电流:2A;峰值拉电流:2A;电源电压:3.3V~20V;上升时间:25ns;下降时间:17ns;")
      (fields (field (name "Manufacturer") "Infineon(英飞凌)"))
      (libsource (lib "easyedapro") (part "IR2110SPBF"))
    )
    (comp (ref "U8")
      (value "AMS1117-5.0")
      (footprint "easyedapro:SOT-223_L6.5-W3.5-P2.30-LS7.0-BR")
      (description "输出类型:固定;最大输入电压:12V;输出电压:5V;最大输出电流:1A;电源纹波抑制比(PSRR):68dB@(120Hz);输出极性:正极;")
      (fields (field (name "Manufacturer") "AMS"))
      (libsource (lib "easyedapro") (part "AMS1117-5.0"))
    )
    (comp (ref "U9")
      (value "AMS1117-3.3")
      (footprint "easyedapro:SOT-223-3_L6.5-W3.4-P2.30-LS7.0-BR")
      (description "输出类型:固定;最大输入电压:-;输出电压:3.3V;最大输出电流:1A;电源纹波抑制比(PSRR):72dB@(120Hz);输出极性:正极;")
      (fields (field (name "Manufacturer") "AMS"))
      (libsource (lib "easyedapro") (part "AMS1117-3.3"))
    )
    (comp (ref "U22")
      (value "2.54-3P接线端子")
      (footprint "easyedapro:CONN-TH_2.54-3P")
      (fields (field (name "Manufacturer") "BOOMELE(博穆精密)"))
      (libsource (lib "easyedapro") (part "2.54-3P"))
    )
  )
  (nets
    (net (code "1") (name "+5V") (class "Default")
      (node (ref "C8") (pin "2") (pinfunction "2_2") (pintype "input"))
      (node (ref "C9") (pin "1") (pinfunction "1_1") (pintype "input"))
      (node (ref "U1") (pin "11") (pinfunction "VDD_11") (pintype "unspecified"))
      (node (ref "U2") (pin "11") (pinfunction "VDD_11") (pintype "unspecified"))
      (node (ref "U3") (pin "11") (pinfunction "VDD_11") (pintype "unspecified"))
      (node (ref "U4") (pin "11") (pinfunction "VDD_11") (pintype "unspecified"))
      (node (ref "U5") (pin "11") (pinfunction "VDD_11") (pintype "unspecified"))
      (node (ref "U6") (pin "11") (pinfunction "VDD_11") (pintype "unspecified"))
      (node (ref "U8") (pin "4") (pinfunction "VOUT_4") (pintype "unspecified"))
      (node (ref "U9") (pin "3") (pinfunction "VIN_3") (pintype "unspecified"))
    )
    (net (code "2") (name "+12V") (class "Default")
      (node (ref "C1") (pin "2") (pinfunction "2_2") (pintype "input"))
      (node (ref "C2") (pin "2") (pinfunction "2_2") (pintype "input"))
      (node (ref "C3") (pin "2") (pinfunction "2_2") (pintype "input"))
      (node (ref "C4") (pin "2") (pinfunction "2_2") (pintype "input"))
      (node (ref "C5") (pin "2") (pinfunction "2_2") (pintype "input"))
      (node (ref "C6") (pin "2") (pinfunction "2_2") (pintype "input"))
      (node (ref "C7") (pin "1") (pinfunction "1_1") (pintype "input"))
      (node (ref "E1") (pin "3") (pinfunction "3_3") (pintype "unspecified"))
      (node (ref "E2") (pin "3") (pinfunction "3_3") (pintype "unspecified"))
      (node (ref "E3") (pin "3") (pinfunction "3_3") (pintype "unspecified"))
      (node (ref "E4") (pin "3") (pinfunction "3_3") (pintype "unspecified"))
      (node (ref "E5") (pin "3") (pinfunction "3_3") (pintype "unspecified"))
      (node (ref "E6") (pin "3") (pinfunction "3_3") (pintype "unspecified"))
      (node (ref "U1") (pin "3") (pinfunction "VCC_3") (pintype "unspecified"))
      (node (ref "U2") (pin "3") (pinfunction "VCC_3") (pintype "unspecified"))
      (node (ref "U22") (pin "2") (pinfunction "2_2") (pintype "unspecified"))
      (node (ref "U3") (pin "3") (pinfunction "VCC_3") (pintype "unspecified"))
      (node (ref "U4") (pin "3") (pinfunction "VCC_3") (pintype "unspecified"))
      (node (ref "U5") (pin "3") (pinfunction "VCC_3") (pintype "unspecified"))
      (node (ref "U6") (pin "3") (pinfunction "VCC_3") (pintype "unspecified"))
      (node (ref "U8") (pin "3") (pinfunction "VIN_3") (pintype "unspecified"))
    )
    (net (code "3") (name "3V3") (class "Default")
      (node (ref "C10") (pin "2") (pinfunction "2_2") (pintype "input"))
      (node (ref "FPC1") (pin "2") (pinfunction "2_2") (pintype "unspecified"))
      (node (ref "U9") (pin "4") (pinfunction "VOUT_4") (pintype "unspecified"))
    )
    (net (code "4") (name "CAP1") (class "Default")
      (node (ref "C11") (pin "1") (pinfunction "1_1") (pintype "input"))
      (node (ref "D2") (pin "1") (pinfunction "1_1") (pintype "input"))
      (node (ref "D25") (pin "1") (pinfunction "C_1") (pintype "unspecified"))
      (node (ref "Q1") (pin "2") (pinfunction "C_2") (pintype "unspecified"))
    )
    (net (code "5") (name "CAP2") (class "Default")
      (node (ref "C12") (pin "1") (pinfunction "1_1") (pintype "input"))
      (node (ref "D26") (pin "1") (pinfunction "C_1") (pintype "unspecified"))
      (node (ref "D5") (pin "1") (pinfunction "1_1") (pintype "input"))
      (node (ref "Q3") (pin "2") (pinfunction "C_2") (pintype "unspecified"))
    )
    (net (code "6") (name "CAP3") (class "Default")
      (node (ref "C13") (pin "1") (pinfunction "1_1") (pintype "input"))
      (node (ref "D27") (pin "1") (pinfunction "C_1") (pintype "unspecified"))
      (node (ref "D9") (pin "1") (pinfunction "1_1") (pintype "input"))
      (node (ref "Q5") (pin "2") (pinfunction "C_2") (pintype "unspecified"))
    )
    (net (code "7") (name "CAP4") (class "Default")
      (node (ref "C14") (pin "1") (pinfunction "1_1") (pintype "input"))
      (node (ref "D13") (pin "1") (pinfunction "1_1") (pintype "input"))
      (node (ref "D28") (pin "1") (pinfunction "C_1") (pintype "unspecified"))
      (node (ref "Q7") (pin "2") (pinfunction "C_2") (pintype "unspecified"))
    )
    (net (code "8") (name "CAP5") (class "Default")
      (node (ref "C15") (pin "1") (pinfunction "1_1") (pintype "input"))
      (node (ref "D17") (pin "1") (pinfunction "1_1") (pintype "input"))
      (node (ref "D29") (pin "1") (pinfunction "C_1") (pintype "unspecified"))
      (node (ref "Q9") (pin "2") (pinfunction "C_2") (pintype "unspecified"))
    )
    (net (code "9") (name "CAP6") (class "Default")
      (node (ref "C16") (pin "1") (pinfunction "1_1") (pintype "input"))
      (node (ref "D21") (pin "1") (pinfunction "1_1") (pintype "input"))
      (node (ref "D30") (pin "1") (pinfunction "C_1") (pintype "unspecified"))
      (node (ref "Q11") (pin "2") (pinfunction "C_2") (pintype "unspecified"))
    )
    (net (code "10") (name "CTRL1") (class "Default")
      (node (ref "CN2") (pin "1") (pinfunction "1_1") (pintype "unspecified"))
      (node (ref "LED1") (pin "1") (pinfunction "A_1") (pintype "unspecified"))
      (node (ref "U1") (pin "12") (pinfunction "HIN_12") (pintype "unspecified"))
      (node (ref "U1") (pin "14") (pinfunction "LIN_14") (pintype "unspecified"))
    )
    (net (code "11") (name "CTRL2") (class "Default")
      (node (ref "CN2") (pin "2") (pinfunction "2_2") (pintype "unspecified"))
      (node (ref "LED2") (pin "1") (pinfunction "A_1") (pintype "unspecified"))
      (node (ref "U2") (pin "12") (pinfunction "HIN_12") (pintype "unspecified"))
      (node (ref "U2") (pin "14") (pinfunction "LIN_14") (pintype "unspecified"))
    )
    (net (code "12") (name "CTRL3") (class "Default")
      (node (ref "CN2") (pin "3") (pinfunction "3_3") (pintype "unspecified"))
      (node (ref "LED3") (pin "1") (pinfunction "A_1") (pintype "unspecified"))
      (node (ref "U3") (pin "12") (pinfunction "HIN_12") (pintype "unspecified"))
      (node (ref "U3") (pin "14") (pinfunction "LIN_14") (pintype "unspecified"))
    )
    (net (code "13") (name "CTRL4") (class "Default")
      (node (ref "CN2") (pin "4") (pinfunction "4_4") (pintype "unspecified"))
      (node (ref "LED4") (pin "1") (pinfunction "A_1") (pintype "unspecified"))
      (node (ref "U4") (pin "12") (pinfunction "HIN_12") (pintype "unspecified"))
      (node (ref "U4") (pin "14") (pinfunction "LIN_14") (pintype "unspecified"))
    )
    (net (code "14") (name "CTRL5") (class "Default")
      (node (ref "CN2") (pin "5") (pinfunction "5_5") (pintype "unspecified"))
      (node (ref "LED5") (pin "1") (pinfunction "A_1") (pintype "unspecified"))
      (node (ref "U5") (pin "12") (pinfunction "HIN_12") (pintype "unspecified"))
      (node (ref "U5") (pin "14") (pinfunction "LIN_14") (pintype "unspecified"))
    )
    (net (code "15") (name "CTRL6") (class "Default")
      (node (ref "CN2") (pin "6") (pinfunction "6_6") (pintype "unspecified"))
      (node (ref "LED6") (pin "1") (pinfunction "A_1") (pintype "unspecified"))
      (node (ref "U6") (pin "12") (pinfunction "HIN_12") (pintype "unspecified"))
      (node (ref "U6") (pin "14") (pinfunction "LIN_14") (pintype "unspecified"))
    )
    (net (code "16") (name "GND") (class "Default")
      (node (ref "C1") (pin "1") (pinfunction "1_1") (pintype "input"))
      (node (ref "C10") (pin "1") (pinfunction "1_1") (pintype "input"))
      (node (ref "C11") (pin "2") (pinfunction "2_2") (pintype "input"))
      (node (ref "C12") (pin "2") (pinfunction "2_2") (pintype "input"))
      (node (ref "C13") (pin "2") (pinfunction "2_2") (pintype "input"))
      (node (ref "C14") (pin "2") (pinfunction "2_2") (pintype "input"))
      (node (ref "C15") (pin "2") (pinfunction "2_2") (pintype "input"))
      (node (ref "C16") (pin "2") (pinfunction "2_2") (pintype "input"))
      (node (ref "C2") (pin "1") (pinfunction "1_1") (pintype "input"))
      (node (ref "C3") (pin "1") (pinfunction "1_1") (pintype "input"))
      (node (ref "C4") (pin "1") (pinfunction "1_1") (pintype "input"))
      (node (ref "C5") (pin "1") (pinfunction "1_1") (pintype "input"))
      (node (ref "C6") (pin "1") (pinfunction "1_1") (pintype "input"))
      (node (ref "C7") (pin "2") (pinfunction "2_2") (pintype "input"))
      (node (ref "C8") (pin "1") (pinfunction "1_1") (pintype "input"))
      (node (ref "C9") (pin "2") (pinfunction "2_2") (pintype "input"))
      (node (ref "D1") (pin "3") (pinfunction "3_3") (pintype "input"))
      (node (ref "D10") (pin "3") (pinfunction "3_3") (pintype "input"))
      (node (ref "D14") (pin "3") (pinfunction "3_3") (pintype "input"))
      (node (ref "D18") (pin "3") (pinfunction "3_3") (pintype "input"))
      (node (ref "D22") (pin "3") (pinfunction "3_3") (pintype "input"))
      (node (ref "D6") (pin "3") (pinfunction "3_3") (pintype "input"))
      (node (ref "E1") (pin "4") (pinfunction "4_4") (pintype "unspecified"))
      (node (ref "E2") (pin "4") (pinfunction "4_4") (pintype "unspecified"))
      (node (ref "E3") (pin "4") (pinfunction "4_4") (pintype "unspecified"))
      (node (ref "E4") (pin "4") (pinfunction "4_4") (pintype "unspecified"))
      (node (ref "E5") (pin "4") (pinfunction "4_4") (pintype "unspecified"))
      (node (ref "E6") (pin "4") (pinfunction "4_4") (pintype "unspecified"))
      (node (ref "FPC1") (pin "1") (pinfunction "1_1") (pintype "unspecified"))
      (node (ref "Q10") (pin "3") (pinfunction "E_3") (pintype "unspecified"))
      (node (ref "Q12") (pin "3") (pinfunction "E_3") (pintype "unspecified"))
      (node (ref "Q2") (pin "3") (pinfunction "E_3") (pintype "unspecified"))
      (node (ref "Q4") (pin "3") (pinfunction "E_3") (pintype "unspecified"))
      (node (ref "Q6") (pin "3") (pinfunction "E_3") (pintype "unspecified"))
      (node (ref "Q8") (pin "3") (pinfunction "E_3") (pintype "unspecified"))
      (node (ref "R12") (pin "1") (pinfunction "1_1") (pintype "input"))
      (node (ref "R15") (pin "1") (pinfunction "1_1") (pintype "input"))
      (node (ref "R18") (pin "1") (pinfunction "1_1") (pintype "input"))
      (node (ref "R3") (pin "1") (pinfunction "1_1") (pintype "input"))
      (node (ref "R6") (pin "1") (pinfunction "1_1") (pintype "input"))
      (node (ref "R9") (pin "1") (pinfunction "1_1") (pintype "input"))
      (node (ref "U1") (pin "13") (pinfunction "SD_13") (pintype "unspecified"))
      (node (ref "U1") (pin "15") (pinfunction "VSS_15") (pintype "unspecified"))
      (node (ref "U1") (pin "2") (pinfunction "COM_2") (pintype "unspecified"))
      (node (ref "U2") (pin "13") (pinfunction "SD_13") (pintype "unspecified"))
      (node (ref "U2") (pin "15") (pinfunction "VSS_15") (pintype "unspecified"))
      (node (ref "U2") (pin "2") (pinfunction "COM_2") (pintype "unspecified"))
      (node (ref "U22") (pin "3") (pinfunction "3_3") (pintype "unspecified"))
      (node (ref "U3") (pin "13") (pinfunction "SD_13") (pintype "unspecified"))
      (node (ref "U3") (pin "15") (pinfunction "VSS_15") (pintype "unspecified"))
      (node (ref "U3") (pin "2") (pinfunction "COM_2") (pintype "unspecified"))
      (node (ref "U4") (pin "13") (pinfunction "SD_13") (pintype "unspecified"))
      (node (ref "U4") (pin "15") (pinfunction "VSS_15") (pintype "unspecified"))
      (node (ref "U4") (pin "2") (pinfunction "COM_2") (pintype "unspecified"))
      (node (ref "U5") (pin "13") (pinfunction "SD_13") (pintype "unspecified"))
      (node (ref "U5") (pin "15") (pinfunction "VSS_15") (pintype "unspecified"))
      (node (ref "U5") (pin "2") (pinfunction "COM_2") (pintype "unspecified"))
      (node (ref "U6") (pin "13") (pinfunction "SD_13") (pintype "unspecified"))
      (node (ref "U6") (pin "15") (pinfunction "VSS_15") (pintype "unspecified"))
      (node (ref "U6") (pin "2") (pinfunction "COM_2") (pintype "unspecified"))
      (node (ref "U8") (pin "1") (pinfunction "GND_1") (pintype "unspecified"))
      (node (ref "U9") (pin "1") (pinfunction "GND_1") (pintype "unspecified"))
    )
    (net (code "17") (name "Net-(CN1-Pad1)") (class "Default")
      (node (ref "CN1") (pin "1") (pinfunction "1_1") (pintype "unspecified"))
      (node (ref "FPC1") (pin "4") (pinfunction "4_4") (pintype "unspecified"))
    )
    (net (code "18") (name "Net-(CN1-Pad2)") (class "Default")
      (node (ref "CN1") (pin "2") (pinfunction "2_2") (pintype "unspecified"))
      (node (ref "FPC1") (pin "3") (pinfunction "3_3") (pintype "unspecified"))
    )
    (net (code "19") (name "Net-(D3-A)") (class "Default")
      (node (ref "D3") (pin "2") (pinfunction "A_2") (pintype "unspecified"))
      (node (ref "Q1") (pin "1") (pinfunction "G_1") (pintype "unspecified"))
      (node (ref "R1") (pin "2") (pinfunction "2_2") (pintype "input"))
    )
    (net (code "20") (name "Net-(D3-K)") (class "Default")
      (node (ref "D3") (pin "1") (pinfunction "K_1") (pintype "unspecified"))
      (node (ref "R1") (pin "1") (pinfunction "1_1") (pintype "input"))
      (node (ref "U1") (pin "8") (pinfunction "HO_8") (pintype "unspecified"))
    )
    (net (code "21") (name "Net-(D4-A)") (class "Default")
      (node (ref "D4") (pin "2") (pinfunction "A_2") (pintype "unspecified"))
      (node (ref "Q2") (pin "1") (pinfunction "G_1") (pintype "unspecified"))
      (node (ref "R2") (pin "2") (pinfunction "2_2") (pintype "input"))
    )
    (net (code "22") (name "Net-(D4-K)") (class "Default")
      (node (ref "D4") (pin "1") (pinfunction "K_1") (pintype "unspecified"))
      (node (ref "R2") (pin "1") (pinfunction "1_1") (pintype "input"))
      (node (ref "U1") (pin "1") (pinfunction "LO_1") (pintype "unspecified"))
    )
    (net (code "23") (name "Net-(D7-A)") (class "Default")
      (node (ref "D7") (pin "2") (pinfunction "A_2") (pintype "unspecified"))
      (node (ref "Q3") (pin "1") (pinfunction "G_1") (pintype "unspecified"))
      (node (ref "R4") (pin "2") (pinfunction "2_2") (pintype "input"))
    )
    (net (code "24") (name "Net-(D7-K)") (class "Default")
      (node (ref "D7") (pin "1") (pinfunction "K_1") (pintype "unspecified"))
      (node (ref "R4") (pin "1") (pinfunction "1_1") (pintype "input"))
      (node (ref "U2") (pin "8") (pinfunction "HO_8") (pintype "unspecified"))
    )
    (net (code "25") (name "Net-(D8-A)") (class "Default")
      (node (ref "D8") (pin "2") (pinfunction "A_2") (pintype "unspecified"))
      (node (ref "Q4") (pin "1") (pinfunction "G_1") (pintype "unspecified"))
      (node (ref "R5") (pin "2") (pinfunction "2_2") (pintype "input"))
    )
    (net (code "26") (name "Net-(D8-K)") (class "Default")
      (node (ref "D8") (pin "1") (pinfunction "K_1") (pintype "unspecified"))
      (node (ref "R5") (pin "1") (pinfunction "1_1") (pintype "input"))
      (node (ref "U2") (pin "1") (pinfunction "LO_1") (pintype "unspecified"))
    )
    (net (code "27") (name "Net-(D11-A)") (class "Default")
      (node (ref "D11") (pin "2") (pinfunction "A_2") (pintype "unspecified"))
      (node (ref "Q5") (pin "1") (pinfunction "G_1") (pintype "unspecified"))
      (node (ref "R7") (pin "2") (pinfunction "2_2") (pintype "input"))
    )
    (net (code "28") (name "Net-(D11-K)") (class "Default")
      (node (ref "D11") (pin "1") (pinfunction "K_1") (pintype "unspecified"))
      (node (ref "R7") (pin "1") (pinfunction "1_1") (pintype "input"))
      (node (ref "U3") (pin "8") (pinfunction "HO_8") (pintype "unspecified"))
    )
    (net (code "29") (name "Net-(D12-A)") (class "Default")
      (node (ref "D12") (pin "2") (pinfunction "A_2") (pintype "unspecified"))
      (node (ref "Q6") (pin "1") (pinfunction "G_1") (pintype "unspecified"))
      (node (ref "R8") (pin "2") (pinfunction "2_2") (pintype "input"))
    )
    (net (code "30") (name "Net-(D12-K)") (class "Default")
      (node (ref "D12") (pin "1") (pinfunction "K_1") (pintype "unspecified"))
      (node (ref "R8") (pin "1") (pinfunction "1_1") (pintype "input"))
      (node (ref "U3") (pin "1") (pinfunction "LO_1") (pintype "unspecified"))
    )
    (net (code "31") (name "Net-(D15-A)") (class "Default")
      (node (ref "D15") (pin "2") (pinfunction "A_2") (pintype "unspecified"))
      (node (ref "Q7") (pin "1") (pinfunction "G_1") (pintype "unspecified"))
      (node (ref "R10") (pin "2") (pinfunction "2_2") (pintype "input"))
    )
    (net (code "32") (name "Net-(D15-K)") (class "Default")
      (node (ref "D15") (pin "1") (pinfunction "K_1") (pintype "unspecified"))
      (node (ref "R10") (pin "1") (pinfunction "1_1") (pintype "input"))
      (node (ref "U4") (pin "8") (pinfunction "HO_8") (pintype "unspecified"))
    )
    (net (code "33") (name "Net-(D16-A)") (class "Default")
      (node (ref "D16") (pin "2") (pinfunction "A_2") (pintype "unspecified"))
      (node (ref "Q8") (pin "1") (pinfunction "G_1") (pintype "unspecified"))
      (node (ref "R11") (pin "2") (pinfunction "2_2") (pintype "input"))
    )
    (net (code "34") (name "Net-(D16-K)") (class "Default")
      (node (ref "D16") (pin "1") (pinfunction "K_1") (pintype "unspecified"))
      (node (ref "R11") (pin "1") (pinfunction "1_1") (pintype "input"))
      (node (ref "U4") (pin "1") (pinfunction "LO_1") (pintype "unspecified"))
    )
    (net (code "35") (name "Net-(D19-A)") (class "Default")
      (node (ref "D19") (pin "2") (pinfunction "A_2") (pintype "unspecified"))
      (node (ref "Q9") (pin "1") (pinfunction "G_1") (pintype "unspecified"))
      (node (ref "R13") (pin "2") (pinfunction "2_2") (pintype "input"))
    )
    (net (code "36") (name "Net-(D19-K)") (class "Default")
      (node (ref "D19") (pin "1") (pinfunction "K_1") (pintype "unspecified"))
      (node (ref "R13") (pin "1") (pinfunction "1_1") (pintype "input"))
      (node (ref "U5") (pin "8") (pinfunction "HO_8") (pintype "unspecified"))
    )
    (net (code "37") (name "Net-(D20-A)") (class "Default")
      (node (ref "D20") (pin "2") (pinfunction "A_2") (pintype "unspecified"))
      (node (ref "Q10") (pin "1") (pinfunction "G_1") (pintype "unspecified"))
      (node (ref "R14") (pin "2") (pinfunction "2_2") (pintype "input"))
    )
    (net (code "38") (name "Net-(D20-K)") (class "Default")
      (node (ref "D20") (pin "1") (pinfunction "K_1") (pintype "unspecified"))
      (node (ref "R14") (pin "1") (pinfunction "1_1") (pintype "input"))
      (node (ref "U5") (pin "1") (pinfunction "LO_1") (pintype "unspecified"))
    )
    (net (code "39") (name "Net-(D23-A)") (class "Default")
      (node (ref "D23") (pin "2") (pinfunction "A_2") (pintype "unspecified"))
      (node (ref "Q11") (pin "1") (pinfunction "G_1") (pintype "unspecified"))
      (node (ref "R16") (pin "2") (pinfunction "2_2") (pintype "input"))
    )
    (net (code "40") (name "Net-(D23-K)") (class "Default")
      (node (ref "D23") (pin "1") (pinfunction "K_1") (pintype "unspecified"))
      (node (ref "R16") (pin "1") (pinfunction "1_1") (pintype "input"))
      (node (ref "U6") (pin "8") (pinfunction "HO_8") (pintype "unspecified"))
    )
    (net (code "41") (name "Net-(D24-A)") (class "Default")
      (node (ref "D24") (pin "2") (pinfunction "A_2") (pintype "unspecified"))
      (node (ref "Q12") (pin "1") (pinfunction "G_1") (pintype "unspecified"))
      (node (ref "R17") (pin "2") (pinfunction "2_2") (pintype "input"))
    )
    (net (code "42") (name "Net-(D24-K)") (class "Default")
      (node (ref "D24") (pin "1") (pinfunction "K_1") (pintype "unspecified"))
      (node (ref "R17") (pin "1") (pinfunction "1_1") (pintype "input"))
      (node (ref "U6") (pin "1") (pinfunction "LO_1") (pintype "unspecified"))
    )
    (net (code "43") (name "Net-(D25-A)") (class "Default")
      (node (ref "D25") (pin "2") (pinfunction "A_2") (pintype "unspecified"))
      (node (ref "D26") (pin "2") (pinfunction "A_2") (pintype "unspecified"))
      (node (ref "D27") (pin "2") (pinfunction "A_2") (pintype "unspecified"))
      (node (ref "D28") (pin "2") (pinfunction "A_2") (pintype "unspecified"))
      (node (ref "D29") (pin "2") (pinfunction "A_2") (pintype "unspecified"))
      (node (ref "D30") (pin "2") (pinfunction "A_2") (pintype "unspecified"))
      (node (ref "U22") (pin "1") (pinfunction "1_1") (pintype "unspecified"))
    )
    (net (code "44") (name "Net-(LED1-K)") (class "Default")
      (node (ref "LED1") (pin "2") (pinfunction "K_2") (pintype "unspecified"))
      (node (ref "R3") (pin "2") (pinfunction "2_2") (pintype "input"))
    )
    (net (code "45") (name "Net-(LED2-K)") (class "Default")
      (node (ref "LED2") (pin "2") (pinfunction "K_2") (pintype "unspecified"))
      (node (ref "R6") (pin "2") (pinfunction "2_2") (pintype "input"))
    )
    (net (code "46") (name "Net-(LED3-K)") (class "Default")
      (node (ref "LED3") (pin "2") (pinfunction "K_2") (pintype "unspecified"))
      (node (ref "R9") (pin "2") (pinfunction "2_2") (pintype "input"))
    )
    (net (code "47") (name "Net-(LED4-K)") (class "Default")
      (node (ref "LED4") (pin "2") (pinfunction "K_2") (pintype "unspecified"))
      (node (ref "R12") (pin "2") (pinfunction "2_2") (pintype "input"))
    )
    (net (code "48") (name "Net-(LED5-K)") (class "Default")
      (node (ref "LED5") (pin "2") (pinfunction "K_2") (pintype "unspecified"))
      (node (ref "R15") (pin "2") (pinfunction "2_2") (pintype "input"))
    )
    (net (code "49") (name "Net-(LED6-K)") (class "Default")
      (node (ref "LED6") (pin "2") (pinfunction "K_2") (pintype "unspecified"))
      (node (ref "R18") (pin "2") (pinfunction "2_2") (pintype "input"))
    )
    (net (code "50") (name "Net-(Q1-E)") (class "Default")
      (node (ref "D1") (pin "1") (pinfunction "1_1") (pintype "input"))
      (node (ref "E1") (pin "2") (pinfunction "2_2") (pintype "unspecified"))
      (node (ref "L1") (pin "1") (pinfunction "1_1") (pintype "unspecified"))
      (node (ref "Q1") (pin "3") (pinfunction "E_3") (pintype "unspecified"))
      (node (ref "U1") (pin "6") (pinfunction "VS_6") (pintype "unspecified"))
    )
    (net (code "51") (name "Net-(Q2-C)") (class "Default")
      (node (ref "D2") (pin "3") (pinfunction "3_3") (pintype "input"))
      (node (ref "L1") (pin "2") (pinfunction "2_2") (pintype "unspecified"))
      (node (ref "Q2") (pin "2") (pinfunction "C_2") (pintype "unspecified"))
    )
    (net (code "52") (name "Net-(Q3-E)") (class "Default")
      (node (ref "D6") (pin "1") (pinfunction "1_1") (pintype "input"))
      (node (ref "E2") (pin "2") (pinfunction "2_2") (pintype "unspecified"))
      (node (ref "L2") (pin "1") (pinfunction "1_1") (pintype "unspecified"))
      (node (ref "Q3") (pin "3") (pinfunction "E_3") (pintype "unspecified"))
      (node (ref "U2") (pin "6") (pinfunction "VS_6") (pintype "unspecified"))
    )
    (net (code "53") (name "Net-(Q4-C)") (class "Default")
      (node (ref "D5") (pin "3") (pinfunction "3_3") (pintype "input"))
      (node (ref "L2") (pin "2") (pinfunction "2_2") (pintype "unspecified"))
      (node (ref "Q4") (pin "2") (pinfunction "C_2") (pintype "unspecified"))
    )
    (net (code "54") (name "Net-(Q5-E)") (class "Default")
      (node (ref "D10") (pin "1") (pinfunction "1_1") (pintype "input"))
      (node (ref "E3") (pin "2") (pinfunction "2_2") (pintype "unspecified"))
      (node (ref "L3") (pin "1") (pinfunction "1_1") (pintype "unspecified"))
      (node (ref "Q5") (pin "3") (pinfunction "E_3") (pintype "unspecified"))
      (node (ref "U3") (pin "6") (pinfunction "VS_6") (pintype "unspecified"))
    )
    (net (code "55") (name "Net-(Q6-C)") (class "Default")
      (node (ref "D9") (pin "3") (pinfunction "3_3") (pintype "input"))
      (node (ref "L3") (pin "2") (pinfunction "2_2") (pintype "unspecified"))
      (node (ref "Q6") (pin "2") (pinfunction "C_2") (pintype "unspecified"))
    )
    (net (code "56") (name "Net-(Q7-E)") (class "Default")
      (node (ref "D14") (pin "1") (pinfunction "1_1") (pintype "input"))
      (node (ref "E4") (pin "2") (pinfunction "2_2") (pintype "unspecified"))
      (node (ref "L4") (pin "1") (pinfunction "1_1") (pintype "unspecified"))
      (node (ref "Q7") (pin "3") (pinfunction "E_3") (pintype "unspecified"))
      (node (ref "U4") (pin "6") (pinfunction "VS_6") (pintype "unspecified"))
    )
    (net (code "57") (name "Net-(Q8-C)") (class "Default")
      (node (ref "D13") (pin "3") (pinfunction "3_3") (pintype "input"))
      (node (ref "L4") (pin "2") (pinfunction "2_2") (pintype "unspecified"))
      (node (ref "Q8") (pin "2") (pinfunction "C_2") (pintype "unspecified"))
    )
    (net (code "58") (name "Net-(Q9-E)") (class "Default")
      (node (ref "D18") (pin "1") (pinfunction "1_1") (pintype "input"))
      (node (ref "E5") (pin "2") (pinfunction "2_2") (pintype "unspecified"))
      (node (ref "L5") (pin "1") (pinfunction "1_1") (pintype "unspecified"))
      (node (ref "Q9") (pin "3") (pinfunction "E_3") (pintype "unspecified"))
      (node (ref "U5") (pin "6") (pinfunction "VS_6") (pintype "unspecified"))
    )
    (net (code "59") (name "Net-(Q10-C)") (class "Default")
      (node (ref "D17") (pin "3") (pinfunction "3_3") (pintype "input"))
      (node (ref "L5") (pin "2") (pinfunction "2_2") (pintype "unspecified"))
      (node (ref "Q10") (pin "2") (pinfunction "C_2") (pintype "unspecified"))
    )
    (net (code "60") (name "Net-(Q11-E)") (class "Default")
      (node (ref "D22") (pin "1") (pinfunction "1_1") (pintype "input"))
      (node (ref "E6") (pin "2") (pinfunction "2_2") (pintype "unspecified"))
      (node (ref "L6") (pin "1") (pinfunction "1_1") (pintype "unspecified"))
      (node (ref "Q11") (pin "3") (pinfunction "E_3") (pintype "unspecified"))
      (node (ref "U6") (pin "6") (pinfunction "VS_6") (pintype "unspecified"))
    )
    (net (code "61") (name "Net-(Q12-C)") (class "Default")
      (node (ref "D21") (pin "3") (pinfunction "3_3") (pintype "input"))
      (node (ref "L6") (pin "2") (pinfunction "2_2") (pintype "unspecified"))
      (node (ref "Q12") (pin "2") (pinfunction "C_2") (pintype "unspecified"))
    )
    (net (code "62") (name "Net-(U1-VB)") (class "Default")
      (node (ref "E1") (pin "1") (pinfunction "1_1") (pintype "unspecified"))
      (node (ref "U1") (pin "7") (pinfunction "VB_7") (pintype "unspecified"))
    )
    (net (code "63") (name "Net-(U2-VB)") (class "Default")
      (node (ref "E2") (pin "1") (pinfunction "1_1") (pintype "unspecified"))
      (node (ref "U2") (pin "7") (pinfunction "VB_7") (pintype "unspecified"))
    )
    (net (code "64") (name "Net-(U3-VB)") (class "Default")
      (node (ref "E3") (pin "1") (pinfunction "1_1") (pintype "unspecified"))
      (node (ref "U3") (pin "7") (pinfunction "VB_7") (pintype "unspecified"))
    )
    (net (code "65") (name "Net-(U4-VB)") (class "Default")
      (node (ref "E4") (pin "1") (pinfunction "1_1") (pintype "unspecified"))
      (node (ref "U4") (pin "7") (pinfunction "VB_7") (pintype "unspecified"))
    )
    (net (code "66") (name "Net-(U5-VB)") (class "Default")
      (node (ref "E5") (pin "1") (pinfunction "1_1") (pintype "unspecified"))
      (node (ref "U5") (pin "7") (pinfunction "VB_7") (pintype "unspecified"))
    )
    (net (code "67") (name "Net-(U6-VB)") (class "Default")
      (node (ref "E6") (pin "1") (pinfunction "1_1") (pintype "unspecified"))
      (node (ref "U6") (pin "7") (pinfunction "VB_7") (pintype "unspecified"))
    )
    (net (code "68") (name "unconnected-(FPC1-Pad5)") (class "Default")
      (node (ref "FPC1") (pin "5") (pinfunction "5_5") (pintype "unspecified"))
    )
    (net (code "69") (name "unconnected-(FPC1-Pad6)") (class "Default")
      (node (ref "FPC1") (pin "6") (pinfunction "6_6") (pintype "unspecified"))
    )
    (net (code "70") (name "unconnected-(U1-NC-Pad4)") (class "Default")
      (node (ref "U1") (pin "4") (pinfunction "NC_4") (pintype "unspecified+no_connect"))
    )
    (net (code "71") (name "unconnected-(U1-NC-Pad5)") (class "Default")
      (node (ref "U1") (pin "5") (pinfunction "NC_5") (pintype "unspecified+no_connect"))
    )
    (net (code "72") (name "unconnected-(U1-NC-Pad9)") (class "Default")
      (node (ref "U1") (pin "9") (pinfunction "NC_9") (pintype "unspecified+no_connect"))
    )
    (net (code "73") (name "unconnected-(U1-NC-Pad10)") (class "Default")
      (node (ref "U1") (pin "10") (pinfunction "NC_10") (pintype "unspecified+no_connect"))
    )
    (net (code "74") (name "unconnected-(U1-NC-Pad16)") (class "Default")
      (node (ref "U1") (pin "16") (pinfunction "NC_16") (pintype "unspecified+no_connect"))
    )
    (net (code "75") (name "unconnected-(U2-NC-Pad4)") (class "Default")
      (node (ref "U2") (pin "4") (pinfunction "NC_4") (pintype "unspecified+no_connect"))
    )
    (net (code "76") (name "unconnected-(U2-NC-Pad5)") (class "Default")
      (node (ref "U2") (pin "5") (pinfunction "NC_5") (pintype "unspecified+no_connect"))
    )
    (net (code "77") (name "unconnected-(U2-NC-Pad9)") (class "Default")
      (node (ref "U2") (pin "9") (pinfunction "NC_9") (pintype "unspecified+no_connect"))
    )
    (net (code "78") (name "unconnected-(U2-NC-Pad10)") (class "Default")
      (node (ref "U2") (pin "10") (pinfunction "NC_10") (pintype "unspecified+no_connect"))
    )
    (net (code "79") (name "unconnected-(U2-NC-Pad16)") (class "Default")
      (node (ref "U2") (pin "16") (pinfunction "NC_16") (pintype "unspecified+no_connect"))
    )
    (net (code "80") (name "unconnected-(U3-NC-Pad4)") (class "Default")
      (node (ref "U3") (pin "4") (pinfunction "NC_4") (pintype "unspecified+no_connect"))
    )
    (net (code "81") (name "unconnected-(U3-NC-Pad5)") (class "Default")
      (node (ref "U3") (pin "5") (pinfunction "NC_5") (pintype "unspecified+no_connect"))
    )
    (net (code "82") (name "unconnected-(U3-NC-Pad9)") (class "Default")
      (node (ref "U3") (pin "9") (pinfunction "NC_9") (pintype "unspecified+no_connect"))
    )
    (net (code "83") (name "unconnected-(U3-NC-Pad10)") (class "Default")
      (node (ref "U3") (pin "10") (pinfunction "NC_10") (pintype "unspecified+no_connect"))
    )
    (net (code "84") (name "unconnected-(U3-NC-Pad16)") (class "Default")
      (node (ref "U3") (pin "16") (pinfunction "NC_16") (pintype "unspecified+no_connect"))
    )
    (net (code "85") (name "unconnected-(U4-NC-Pad4)") (class "Default")
      (node (ref "U4") (pin "4") (pinfunction "NC_4") (pintype "unspecified+no_connect"))
    )
    (net (code "86") (name "unconnected-(U4-NC-Pad5)") (class "Default")
      (node (ref "U4") (pin "5") (pinfunction "NC_5") (pintype "unspecified+no_connect"))
    )
    (net (code "87") (name "unconnected-(U4-NC-Pad9)") (class "Default")
      (node (ref "U4") (pin "9") (pinfunction "NC_9") (pintype "unspecified+no_connect"))
    )
    (net (code "88") (name "unconnected-(U4-NC-Pad10)") (class "Default")
      (node (ref "U4") (pin "10") (pinfunction "NC_10") (pintype "unspecified+no_connect"))
    )
    (net (code "89") (name "unconnected-(U4-NC-Pad16)") (class "Default")
      (node (ref "U4") (pin "16") (pinfunction "NC_16") (pintype "unspecified+no_connect"))
    )
    (net (code "90") (name "unconnected-(U5-NC-Pad4)") (class "Default")
      (node (ref "U5") (pin "4") (pinfunction "NC_4") (pintype "unspecified+no_connect"))
    )
    (net (code "91") (name "unconnected-(U5-NC-Pad5)") (class "Default")
      (node (ref "U5") (pin "5") (pinfunction "NC_5") (pintype "unspecified+no_connect"))
    )
    (net (code "92") (name "unconnected-(U5-NC-Pad9)") (class "Default")
      (node (ref "U5") (pin "9") (pinfunction "NC_9") (pintype "unspecified+no_connect"))
    )
    (net (code "93") (name "unconnected-(U5-NC-Pad10)") (class "Default")
      (node (ref "U5") (pin "10") (pinfunction "NC_10") (pintype "unspecified+no_connect"))
    )
    (net (code "94") (name "unconnected-(U5-NC-Pad16)") (class "Default")
      (node (ref "U5") (pin "16") (pinfunction "NC_16") (pintype "unspecified+no_connect"))
    )
    (net (code "95") (name "unconnected-(U6-NC-Pad4)") (class "Default")
      (node (ref "U6") (pin "4") (pinfunction "NC_4") (pintype "unspecified+no_connect"))
    )
    (net (code "96") (name "unconnected-(U6-NC-Pad5)") (class "Default")
      (node (ref "U6") (pin "5") (pinfunction "NC_5") (pintype "unspecified+no_connect"))
    )
    (net (code "97") (name "unconnected-(U6-NC-Pad9)") (class "Default")
      (node (ref "U6") (pin "9") (pinfunction "NC_9") (pintype "unspecified+no_connect"))
    )
    (net (code "98") (name "unconnected-(U6-NC-Pad10)") (class "Default")
      (node (ref "U6") (pin "10") (pinfunction "NC_10") (pintype "unspecified+no_connect"))
    )
    (net (code "99") (name "unconnected-(U6-NC-Pad16)") (class "Default")
      (node (ref "U6") (pin "16") (pinfunction "NC_16") (pintype "unspecified+no_connect"))
    )
    (net (code "100") (name "unconnected-(U8-VOUT-Pad2)") (class "Default")
      (node (ref "U8") (pin "2") (pinfunction "VOUT_2") (pintype "unspecified+no_connect"))
    )
    (net (code "101") (name "unconnected-(U9-VOUT-Pad2)") (class "Default")
      (node (ref "U9") (pin "2") (pinfunction "VOUT_2") (pintype "unspecified+no_connect"))
    )
  )
)
